# UsbAtMega.net
KiCad netlist of a schematic drawn in EAGLE
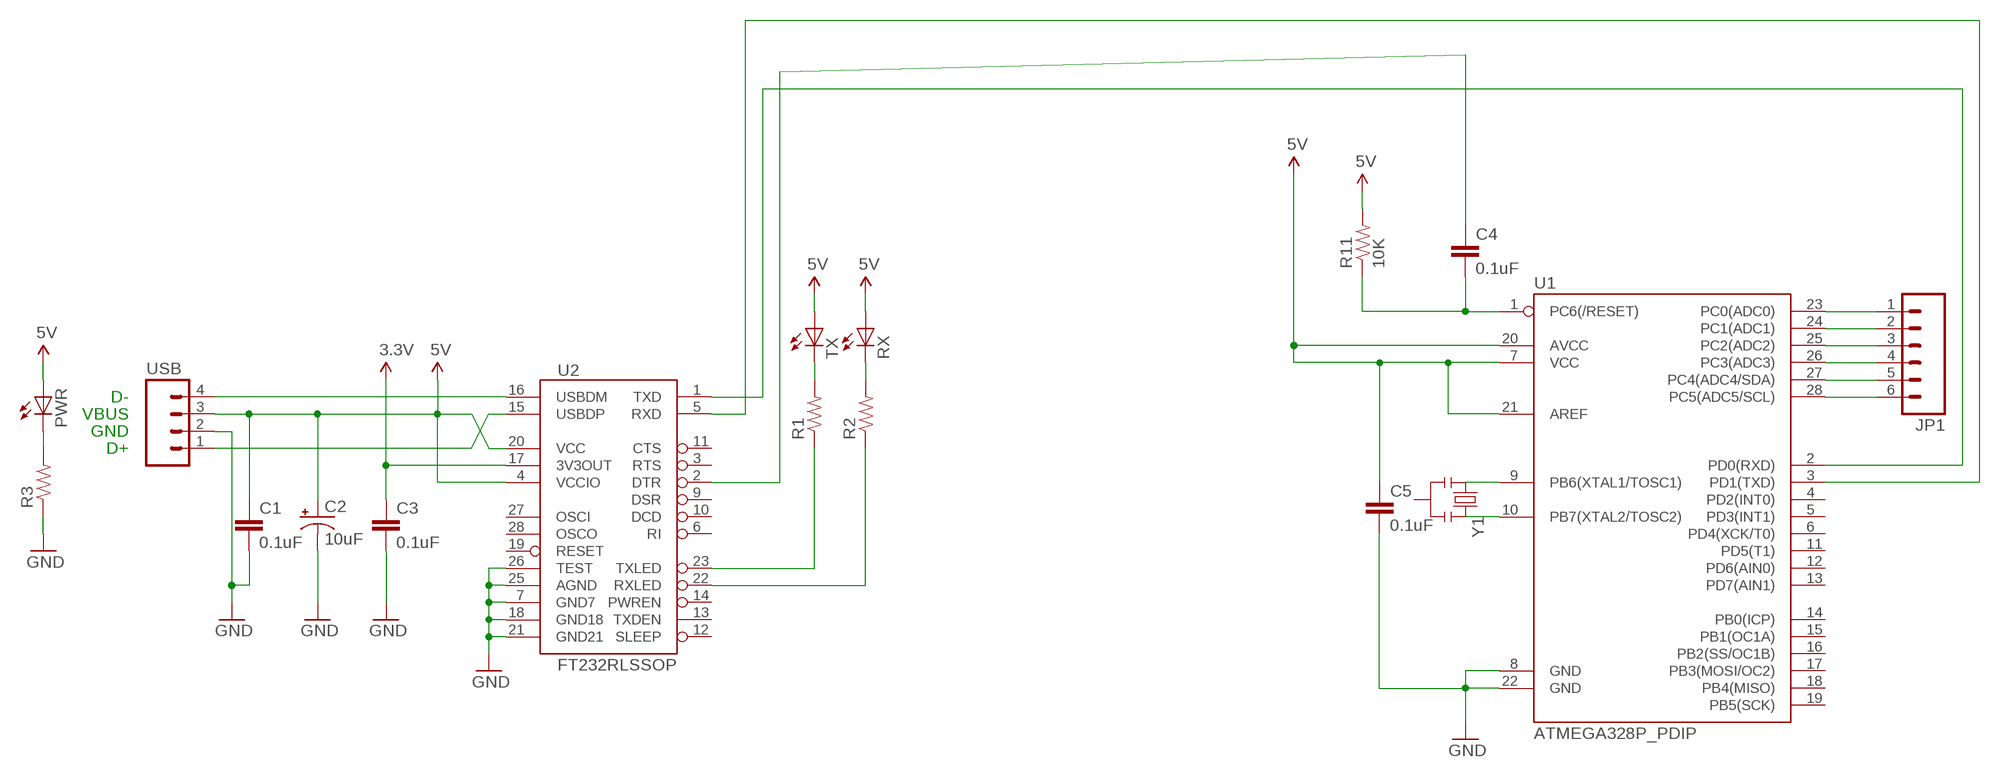
[diagram p0: schematic, sheet 1]

(export (version "E")
  (design (tool "Eeschema 10.0.6"))
  (components
    (comp (ref "C1")
      (value "0.1uF")
      (footprint "eagle-import:CAP-PTH-SMALLEZ")
      (libsource (lib "eagle-import") (part "CAPEZ"))
    )
    (comp (ref "C2")
      (value "10uF")
      (footprint "eagle-import:CPOL-RADIAL-10UF-25V")
      (libsource (lib "eagle-import") (part "CAP_POLPTH2"))
    )
    (comp (ref "C3")
      (value "0.1uF")
      (footprint "eagle-import:CAP-PTH-SMALLEZ")
      (libsource (lib "eagle-import") (part "CAPEZ"))
    )
    (comp (ref "C4")
      (value "0.1uF")
      (footprint "eagle-import:CAP-PTH-SMALL")
      (libsource (lib "eagle-import") (part "SparkFun-Passives_CAPPTH"))
    )
    (comp (ref "C5")
      (value "0.1uF")
      (footprint "eagle-import:CAP-PTH-SMALL")
      (libsource (lib "eagle-import") (part "SparkFun-Passives_CAPPTH"))
    )
    (comp (ref "JP1")
      (value "M06SIP")
      (footprint "eagle-import:1X06")
      (libsource (lib "eagle-import") (part "M06SIP"))
    )
    (comp (ref "PWR")
      (value "LED5MM")
      (footprint "eagle-import:LED5MM")
      (libsource (lib "eagle-import") (part "LED5MM"))
    )
    (comp (ref "R1")
      (value "10KOHM1/6W5%(PTH)KIT")
      (footprint "eagle-import:AXIAL-0.3-KIT")
      (libsource (lib "eagle-import") (part "10KOHM1/6W5%(PTH)KIT"))
    )
    (comp (ref "R2")
      (value "10KOHM1/6W5%(PTH)KIT")
      (footprint "eagle-import:AXIAL-0.3-KIT")
      (libsource (lib "eagle-import") (part "10KOHM1/6W5%(PTH)KIT"))
    )
    (comp (ref "R3")
      (value "10KOHM1/6W5%(PTH)KIT")
      (footprint "eagle-import:AXIAL-0.3-KIT")
      (libsource (lib "eagle-import") (part "10KOHM1/6W5%(PTH)KIT"))
    )
    (comp (ref "R11")
      (value "10K")
      (footprint "eagle-import:AXIAL-0.3")
      (libsource (lib "eagle-import") (part "RESISTORAXIAL-0.3"))
    )
    (comp (ref "RX")
      (value "LED5MM")
      (footprint "eagle-import:LED5MM")
      (libsource (lib "eagle-import") (part "LED5MM"))
    )
    (comp (ref "TX")
      (value "LED5MM")
      (footprint "eagle-import:LED5MM")
      (libsource (lib "eagle-import") (part "LED5MM"))
    )
    (comp (ref "U1")
      (value "ATMEGA328P_PDIP")
      (footprint "eagle-import:DIL28-3")
      (libsource (lib "eagle-import") (part "ATMEGA328P_PDIP"))
    )
    (comp (ref "U2")
      (value "FT232RLSSOP")
      (footprint "eagle-import:SSOP28DB")
      (libsource (lib "eagle-import") (part "FT232RLSSOP"))
    )
    (comp (ref "USB")
      (value "M04LOCK")
      (footprint "eagle-import:1X04_LOCK")
      (libsource (lib "eagle-import") (part "M04LOCK"))
    )
    (comp (ref "Y1")
      (value "RESONATORPTH")
      (footprint "eagle-import:RESONATOR-PTH")
      (libsource (lib "eagle-import") (part "RESONATORPTH"))
    )
  )
  (nets
    (net (code "1") (name "3.3V") (class "Default")
      (node (ref "C3") (pin "1") (pinfunction "1_1") (pintype "passive"))
      (node (ref "U2") (pin "17") (pinfunction "3V3OUT_17") (pintype "output"))
    )
    (net (code "2") (name "5V") (class "Default")
      (node (ref "C1") (pin "1") (pinfunction "1_1") (pintype "passive"))
      (node (ref "C2") (pin "1") (pinfunction "+_1") (pintype "passive"))
      (node (ref "C5") (pin "1") (pinfunction "1_1") (pintype "passive"))
      (node (ref "PWR") (pin "A") (pinfunction "A_A") (pintype "passive"))
      (node (ref "R11") (pin "P$2") (pinfunction "2_P$2") (pintype "passive"))
      (node (ref "RX") (pin "A") (pinfunction "A_A") (pintype "passive"))
      (node (ref "TX") (pin "A") (pinfunction "A_A") (pintype "passive"))
      (node (ref "U1") (pin "20") (pinfunction "AVCC_20") (pintype "bidirectional"))
      (node (ref "U1") (pin "21") (pinfunction "AREF_21") (pintype "bidirectional"))
      (node (ref "U1") (pin "7") (pinfunction "VCC_7") (pintype "bidirectional"))
      (node (ref "U2") (pin "20") (pinfunction "VCC_20") (pintype "power_in"))
      (node (ref "U2") (pin "4") (pinfunction "VCCIO_4") (pintype "power_in"))
      (node (ref "USB") (pin "3") (pinfunction "3_3") (pintype "passive"))
    )
    (net (code "3") (name "GND") (class "Default")
      (node (ref "C1") (pin "2") (pinfunction "2_2") (pintype "passive"))
      (node (ref "C2") (pin "2") (pinfunction "-_2") (pintype "passive"))
      (node (ref "C3") (pin "2") (pinfunction "2_2") (pintype "passive"))
      (node (ref "C5") (pin "2") (pinfunction "2_2") (pintype "passive"))
      (node (ref "R3") (pin "P$1") (pinfunction "1_P$1") (pintype "passive"))
      (node (ref "U1") (pin "22") (pinfunction "GND_22") (pintype "bidirectional"))
      (node (ref "U1") (pin "8") (pinfunction "GND_8") (pintype "bidirectional"))
      (node (ref "U2") (pin "18") (pinfunction "GND18_18") (pintype "power_in"))
      (node (ref "U2") (pin "21") (pinfunction "GND21_21") (pintype "power_in"))
      (node (ref "U2") (pin "25") (pinfunction "AGND_25") (pintype "power_in"))
      (node (ref "U2") (pin "26") (pinfunction "TEST_26") (pintype "input"))
      (node (ref "U2") (pin "7") (pinfunction "GND7_7") (pintype "power_in"))
      (node (ref "USB") (pin "2") (pinfunction "2_2") (pintype "passive"))
    )
    (net (code "4") (name "Net-(PWR-C)") (class "Default")
      (node (ref "PWR") (pin "K") (pinfunction "C_K") (pintype "passive"))
      (node (ref "R3") (pin "P$2") (pinfunction "2_P$2") (pintype "passive"))
    )
    (net (code "5") (name "Net-(R1-1)") (class "Default")
      (node (ref "R1") (pin "P$1") (pinfunction "1_P$1") (pintype "passive"))
      (node (ref "U2") (pin "23") (pinfunction "TXLED_23") (pintype "input"))
    )
    (net (code "6") (name "Net-(R1-2)") (class "Default")
      (node (ref "R1") (pin "P$2") (pinfunction "2_P$2") (pintype "passive"))
      (node (ref "TX") (pin "K") (pinfunction "C_K") (pintype "passive"))
    )
    (net (code "7") (name "Net-(R2-1)") (class "Default")
      (node (ref "R2") (pin "P$1") (pinfunction "1_P$1") (pintype "passive"))
      (node (ref "U2") (pin "22") (pinfunction "RXLED_22") (pintype "input"))
    )
    (net (code "8") (name "Net-(R2-2)") (class "Default")
      (node (ref "R2") (pin "P$2") (pinfunction "2_P$2") (pintype "passive"))
      (node (ref "RX") (pin "K") (pinfunction "C_K") (pintype "passive"))
    )
    (net (code "9") (name "Net-(R11-1)") (class "Default")
      (node (ref "C4") (pin "2") (pinfunction "2_2") (pintype "passive"))
      (node (ref "R11") (pin "P$1") (pinfunction "1_P$1") (pintype "passive"))
      (node (ref "U1") (pin "1") (pinfunction "PC6(/RESET)_1") (pintype "bidirectional"))
    )
    (net (code "10") (name "Net-(U1-PB6(XTAL1{slash}TOSC1))") (class "Default")
      (node (ref "U1") (pin "9") (pinfunction "PB6(XTAL1/TOSC1)_9") (pintype "bidirectional"))
      (node (ref "Y1") (pin "1") (pinfunction "1_1") (pintype "passive"))
    )
    (net (code "11") (name "Net-(U1-PB7(XTAL2{slash}TOSC2))") (class "Default")
      (node (ref "U1") (pin "10") (pinfunction "PB7(XTAL2/TOSC2)_10") (pintype "bidirectional"))
      (node (ref "Y1") (pin "3") (pinfunction "3_3") (pintype "passive"))
    )
    (net (code "12") (name "Net-(U1-PC0(ADC0))") (class "Default")
      (node (ref "JP1") (pin "1") (pinfunction "1_1") (pintype "passive"))
      (node (ref "U1") (pin "23") (pinfunction "PC0(ADC0)_23") (pintype "bidirectional"))
    )
    (net (code "13") (name "Net-(U1-PC1(ADC1))") (class "Default")
      (node (ref "JP1") (pin "2") (pinfunction "2_2") (pintype "passive"))
      (node (ref "U1") (pin "24") (pinfunction "PC1(ADC1)_24") (pintype "bidirectional"))
    )
    (net (code "14") (name "Net-(U1-PC2(ADC2))") (class "Default")
      (node (ref "JP1") (pin "3") (pinfunction "3_3") (pintype "passive"))
      (node (ref "U1") (pin "25") (pinfunction "PC2(ADC2)_25") (pintype "bidirectional"))
    )
    (net (code "15") (name "Net-(U1-PC3(ADC3))") (class "Default")
      (node (ref "JP1") (pin "4") (pinfunction "4_4") (pintype "passive"))
      (node (ref "U1") (pin "26") (pinfunction "PC3(ADC3)_26") (pintype "bidirectional"))
    )
    (net (code "16") (name "Net-(U1-PC4(ADC4{slash}SDA))") (class "Default")
      (node (ref "JP1") (pin "5") (pinfunction "5_5") (pintype "passive"))
      (node (ref "U1") (pin "27") (pinfunction "PC4(ADC4/SDA)_27") (pintype "bidirectional"))
    )
    (net (code "17") (name "Net-(U1-PC5(ADC5{slash}SCL))") (class "Default")
      (node (ref "JP1") (pin "6") (pinfunction "6_6") (pintype "passive"))
      (node (ref "U1") (pin "28") (pinfunction "PC5(ADC5/SCL)_28") (pintype "bidirectional"))
    )
    (net (code "18") (name "Net-(U1-PD0(RXD))") (class "Default")
      (node (ref "U1") (pin "2") (pinfunction "PD0(RXD)_2") (pintype "bidirectional"))
      (node (ref "U2") (pin "1") (pinfunction "TXD_1") (pintype "output"))
    )
    (net (code "19") (name "Net-(U1-PD1(TXD))") (class "Default")
      (node (ref "U1") (pin "3") (pinfunction "PD1(TXD)_3") (pintype "bidirectional"))
      (node (ref "U2") (pin "5") (pinfunction "RXD_5") (pintype "input"))
    )
    (net (code "20") (name "Net-(U2-DTR)") (class "Default")
      (node (ref "C4") (pin "1") (pinfunction "1_1") (pintype "passive"))
      (node (ref "U2") (pin "2") (pinfunction "DTR_2") (pintype "output"))
    )
    (net (code "21") (name "Net-(U2-USBDM)") (class "Default")
      (node (ref "U2") (pin "16") (pinfunction "USBDM_16") (pintype "bidirectional"))
      (node (ref "USB") (pin "4") (pinfunction "4_4") (pintype "passive"))
    )
    (net (code "22") (name "Net-(U2-USBDP)") (class "Default")
      (node (ref "U2") (pin "15") (pinfunction "USBDP_15") (pintype "bidirectional"))
      (node (ref "USB") (pin "1") (pinfunction "1_1") (pintype "passive"))
    )
    (net (code "23") (name "unconnected-(U1-PB0(ICP)-Pad14)") (class "Default")
      (node (ref "U1") (pin "14") (pinfunction "PB0(ICP)_14") (pintype "bidirectional"))
    )
    (net (code "24") (name "unconnected-(U1-PB1(OC1A)-Pad15)") (class "Default")
      (node (ref "U1") (pin "15") (pinfunction "PB1(OC1A)_15") (pintype "bidirectional"))
    )
    (net (code "25") (name "unconnected-(U1-PB2(SS{slash}OC1B)-Pad16)") (class "Default")
      (node (ref "U1") (pin "16") (pinfunction "PB2(SS/OC1B)_16") (pintype "bidirectional"))
    )
    (net (code "26") (name "unconnected-(U1-PB3(MOSI{slash}OC2)-Pad17)") (class "Default")
      (node (ref "U1") (pin "17") (pinfunction "PB3(MOSI/OC2)_17") (pintype "bidirectional"))
    )
    (net (code "27") (name "unconnected-(U1-PB4(MISO)-Pad18)") (class "Default")
      (node (ref "U1") (pin "18") (pinfunction "PB4(MISO)_18") (pintype "bidirectional"))
    )
    (net (code "28") (name "unconnected-(U1-PB5(SCK)-Pad19)") (class "Default")
      (node (ref "U1") (pin "19") (pinfunction "PB5(SCK)_19") (pintype "bidirectional"))
    )
    (net (code "29") (name "unconnected-(U1-PD2(INT0)-Pad4)") (class "Default")
      (node (ref "U1") (pin "4") (pinfunction "PD2(INT0)_4") (pintype "bidirectional"))
    )
    (net (code "30") (name "unconnected-(U1-PD3(INT1)-Pad5)") (class "Default")
      (node (ref "U1") (pin "5") (pinfunction "PD3(INT1)_5") (pintype "bidirectional"))
    )
    (net (code "31") (name "unconnected-(U1-PD4(XCK{slash}T0)-Pad6)") (class "Default")
      (node (ref "U1") (pin "6") (pinfunction "PD4(XCK/T0)_6") (pintype "bidirectional"))
    )
    (net (code "32") (name "unconnected-(U1-PD5(T1)-Pad11)") (class "Default")
      (node (ref "U1") (pin "11") (pinfunction "PD5(T1)_11") (pintype "bidirectional"))
    )
    (net (code "33") (name "unconnected-(U1-PD6(AIN0)-Pad12)") (class "Default")
      (node (ref "U1") (pin "12") (pinfunction "PD6(AIN0)_12") (pintype "bidirectional"))
    )
    (net (code "34") (name "unconnected-(U1-PD7(AIN1)-Pad13)") (class "Default")
      (node (ref "U1") (pin "13") (pinfunction "PD7(AIN1)_13") (pintype "bidirectional"))
    )
    (net (code "35") (name "unconnected-(U2-CTS-Pad11)") (class "Default")
      (node (ref "U2") (pin "11") (pinfunction "CTS_11") (pintype "input"))
    )
    (net (code "36") (name "unconnected-(U2-DCD-Pad10)") (class "Default")
      (node (ref "U2") (pin "10") (pinfunction "DCD_10") (pintype "input"))
    )
    (net (code "37") (name "unconnected-(U2-DSR-Pad9)") (class "Default")
      (node (ref "U2") (pin "9") (pinfunction "DSR_9") (pintype "input"))
    )
    (net (code "38") (name "unconnected-(U2-OSCI-Pad27)") (class "Default")
      (node (ref "U2") (pin "27") (pinfunction "OSCI_27") (pintype "input"))
    )
    (net (code "39") (name "unconnected-(U2-OSCO-Pad28)") (class "Default")
      (node (ref "U2") (pin "28") (pinfunction "OSCO_28") (pintype "output"))
    )
    (net (code "40") (name "unconnected-(U2-PWREN-Pad14)") (class "Default")
      (node (ref "U2") (pin "14") (pinfunction "PWREN_14") (pintype "input"))
    )
    (net (code "41") (name "unconnected-(U2-RESET-Pad19)") (class "Default")
      (node (ref "U2") (pin "19") (pinfunction "RESET_19") (pintype "input"))
    )
    (net (code "42") (name "unconnected-(U2-RI-Pad6)") (class "Default")
      (node (ref "U2") (pin "6") (pinfunction "RI_6") (pintype "input"))
    )
    (net (code "43") (name "unconnected-(U2-RTS-Pad3)") (class "Default")
      (node (ref "U2") (pin "3") (pinfunction "RTS_3") (pintype "output"))
    )
    (net (code "44") (name "unconnected-(U2-SLEEP-Pad12)") (class "Default")
      (node (ref "U2") (pin "12") (pinfunction "SLEEP_12") (pintype "input"))
    )
    (net (code "45") (name "unconnected-(U2-TXDEN-Pad13)") (class "Default")
      (node (ref "U2") (pin "13") (pinfunction "TXDEN_13") (pintype "input"))
    )
    (net (code "46") (name "unconnected-(Y1-Pad2)") (class "Default")
      (node (ref "Y1") (pin "2") (pinfunction "2_2") (pintype "passive"))
    )
  )
)
